# main_pcb_v2.net
KiCad netlist of a schematic drawn in EAGLE
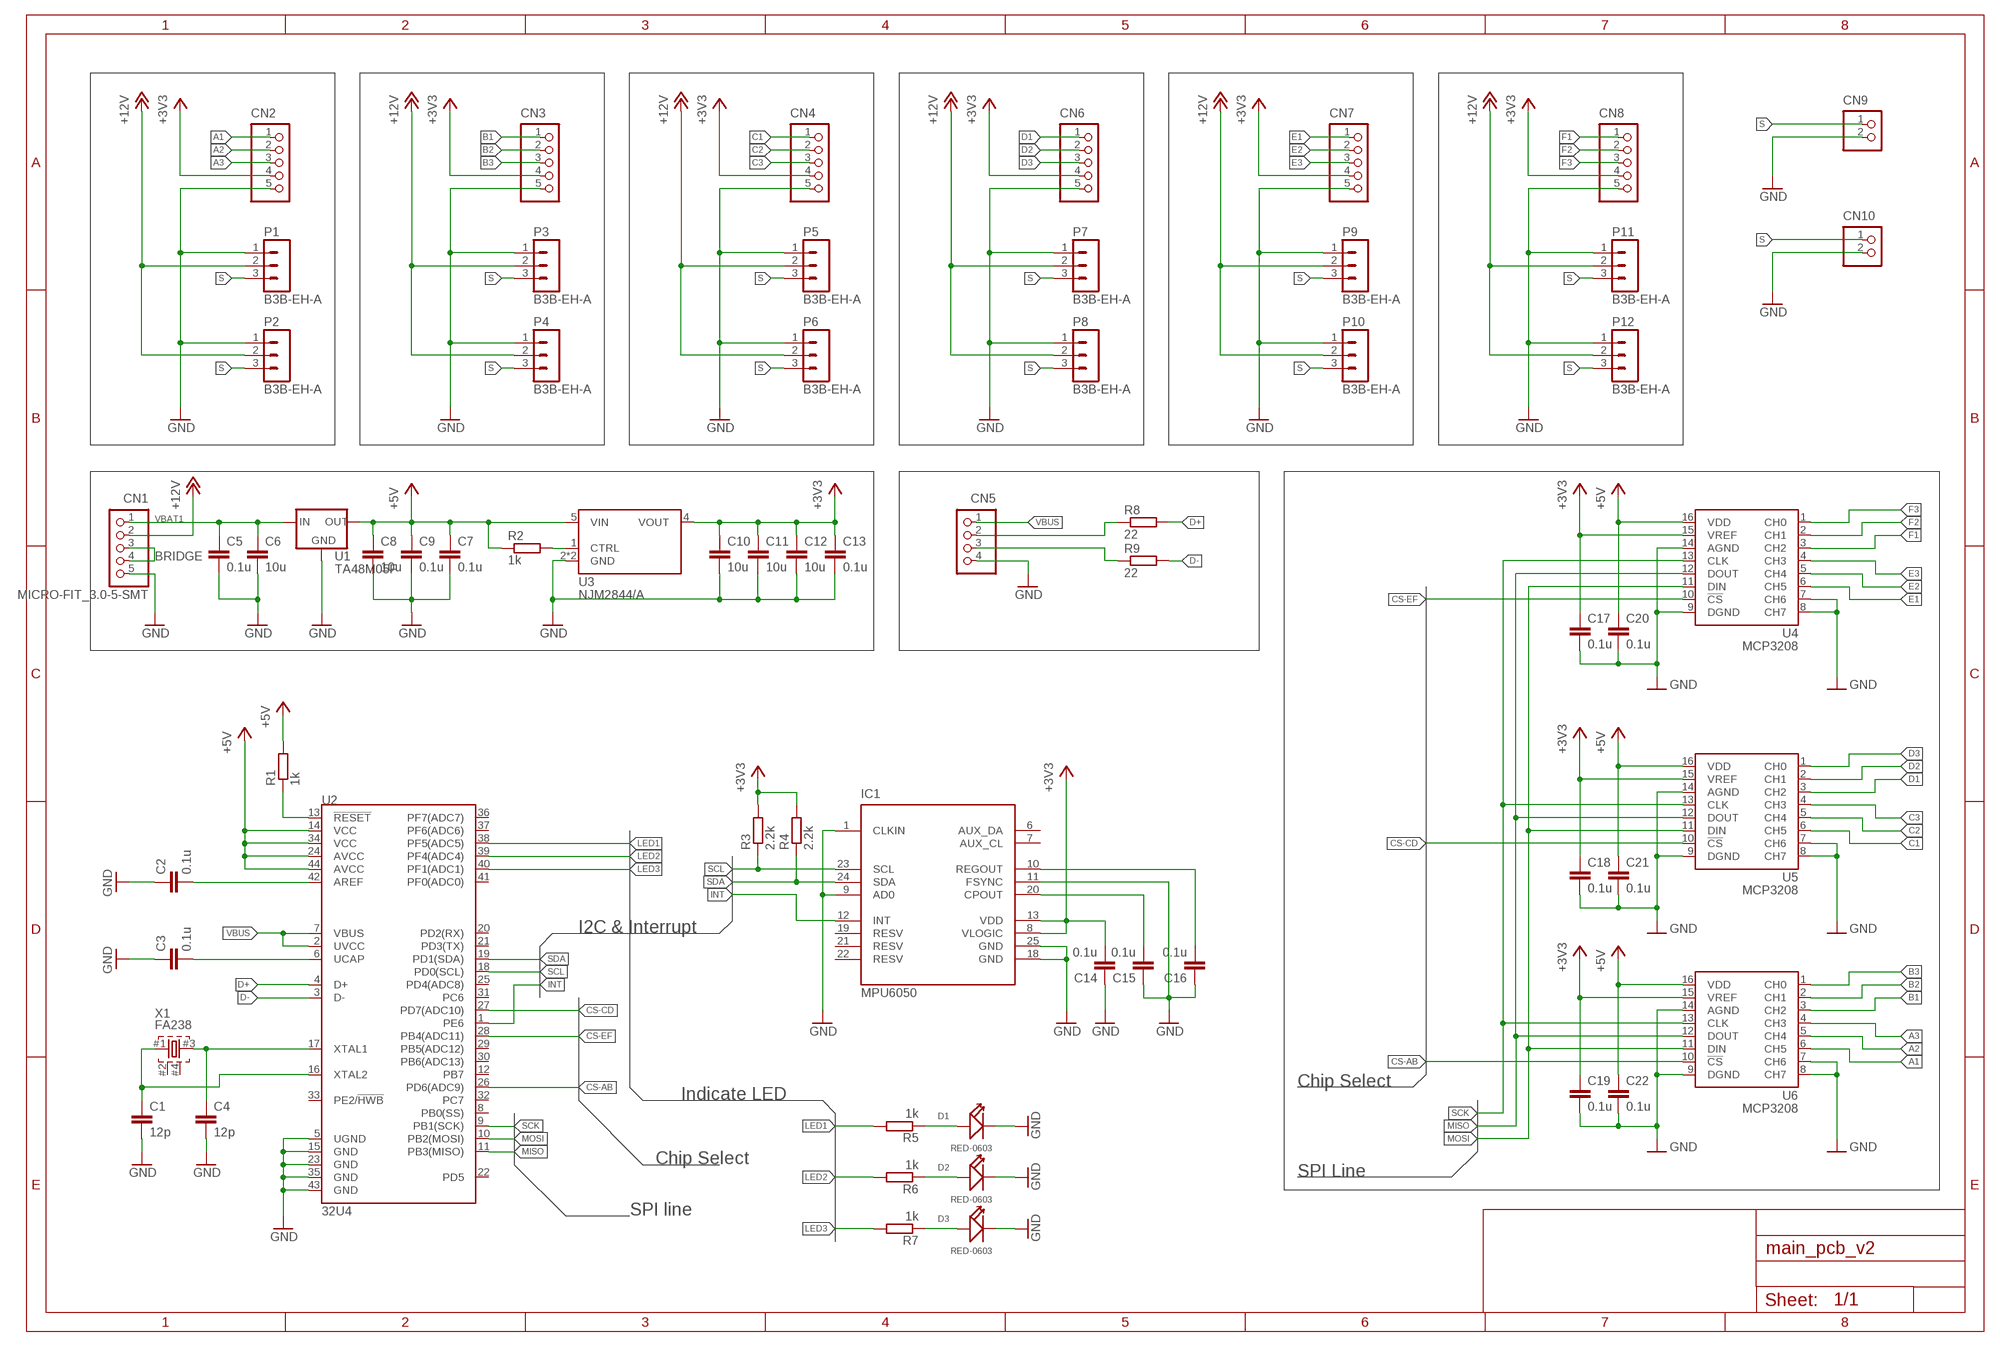
[diagram p0: schematic, sheet 1]

(export (version "E")
  (design (tool "Eeschema 10.0.6"))
  (components
    (comp (ref "C1")
      (value "12p")
      (footprint "eagle-import:C0603")
      (libsource (lib "eagle-import") (part "C-EUC0603"))
    )
    (comp (ref "C2")
      (value "0.1u")
      (footprint "eagle-import:C0603")
      (libsource (lib "eagle-import") (part "C-EUC0603"))
    )
    (comp (ref "C3")
      (value "0.1u")
      (footprint "eagle-import:C0603")
      (libsource (lib "eagle-import") (part "C-EUC0603"))
    )
    (comp (ref "C4")
      (value "12p")
      (footprint "eagle-import:C0603")
      (libsource (lib "eagle-import") (part "C-EUC0603"))
    )
    (comp (ref "C5")
      (value "0.1u")
      (footprint "eagle-import:C0603")
      (libsource (lib "eagle-import") (part "C-EUC0603"))
    )
    (comp (ref "C6")
      (value "10u")
      (footprint "eagle-import:C0805")
      (libsource (lib "eagle-import") (part "C-EUC0805"))
    )
    (comp (ref "C7")
      (value "0.1u")
      (footprint "eagle-import:C0603")
      (libsource (lib "eagle-import") (part "C-EUC0603"))
    )
    (comp (ref "C8")
      (value "10u")
      (footprint "eagle-import:C0805")
      (libsource (lib "eagle-import") (part "C-EUC0805"))
    )
    (comp (ref "C9")
      (value "0.1u")
      (footprint "eagle-import:C0603")
      (libsource (lib "eagle-import") (part "C-EUC0603"))
    )
    (comp (ref "C10")
      (value "10u")
      (footprint "eagle-import:C0805")
      (libsource (lib "eagle-import") (part "C-EUC0805"))
    )
    (comp (ref "C11")
      (value "10u")
      (footprint "eagle-import:C0805")
      (libsource (lib "eagle-import") (part "C-EUC0805"))
    )
    (comp (ref "C12")
      (value "10u")
      (footprint "eagle-import:C0805")
      (libsource (lib "eagle-import") (part "C-EUC0805"))
    )
    (comp (ref "C13")
      (value "0.1u")
      (footprint "eagle-import:C0603")
      (libsource (lib "eagle-import") (part "C-EUC0603"))
    )
    (comp (ref "C14")
      (value "0.1u")
      (footprint "eagle-import:C0603")
      (libsource (lib "eagle-import") (part "C-EUC0603"))
    )
    (comp (ref "C15")
      (value "0.1u")
      (footprint "eagle-import:C0603")
      (libsource (lib "eagle-import") (part "C-EUC0603"))
    )
    (comp (ref "C16")
      (value "0.1u")
      (footprint "eagle-import:C0603")
      (libsource (lib "eagle-import") (part "C-EUC0603"))
    )
    (comp (ref "C17")
      (value "0.1u")
      (footprint "eagle-import:C0603")
      (libsource (lib "eagle-import") (part "C-EUC0603"))
    )
    (comp (ref "C18")
      (value "0.1u")
      (footprint "eagle-import:C0603")
      (libsource (lib "eagle-import") (part "C-EUC0603"))
    )
    (comp (ref "C19")
      (value "0.1u")
      (footprint "eagle-import:C0603")
      (libsource (lib "eagle-import") (part "C-EUC0603"))
    )
    (comp (ref "C20")
      (value "0.1u")
      (footprint "eagle-import:C0603")
      (libsource (lib "eagle-import") (part "C-EUC0603"))
    )
    (comp (ref "C21")
      (value "0.1u")
      (footprint "eagle-import:C0603")
      (libsource (lib "eagle-import") (part "C-EUC0603"))
    )
    (comp (ref "C22")
      (value "0.1u")
      (footprint "eagle-import:C0603")
      (libsource (lib "eagle-import") (part "C-EUC0603"))
    )
    (comp (ref "CN1")
      (value "MICRO-FIT_3.0-5-SMT")
      (footprint "eagle-import:MICRO-FIT_3.0-5_SMT")
      (libsource (lib "eagle-import") (part "MICRO-FIT_3.0-5-SMT"))
    )
    (comp (ref "CN2")
      (value "B5B-PH-K-S")
      (footprint "eagle-import:B5B-PH-K-S")
      (libsource (lib "eagle-import") (part "B5B-PH-K-S"))
    )
    (comp (ref "CN3")
      (value "B5B-PH-K-S")
      (footprint "eagle-import:B5B-PH-K-S")
      (libsource (lib "eagle-import") (part "B5B-PH-K-S"))
    )
    (comp (ref "CN4")
      (value "B5B-PH-K-S")
      (footprint "eagle-import:B5B-PH-K-S")
      (libsource (lib "eagle-import") (part "B5B-PH-K-S"))
    )
    (comp (ref "CN5")
      (value "S4B-PH-K-S")
      (footprint "eagle-import:S4B-PH-K-S")
      (libsource (lib "eagle-import") (part "S4B-PH-K-S"))
    )
    (comp (ref "CN6")
      (value "B5B-PH-K-S")
      (footprint "eagle-import:B5B-PH-K-S")
      (libsource (lib "eagle-import") (part "B5B-PH-K-S"))
    )
    (comp (ref "CN7")
      (value "B5B-PH-K-S")
      (footprint "eagle-import:B5B-PH-K-S")
      (libsource (lib "eagle-import") (part "B5B-PH-K-S"))
    )
    (comp (ref "CN8")
      (value "B5B-PH-K-S")
      (footprint "eagle-import:B5B-PH-K-S")
      (libsource (lib "eagle-import") (part "B5B-PH-K-S"))
    )
    (comp (ref "CN9")
      (value "B2B-PH-K-S")
      (footprint "eagle-import:B2B-PH-K-S")
      (libsource (lib "eagle-import") (part "B2B-PH-K-S"))
    )
    (comp (ref "CN10")
      (value "B2B-PH-K-S")
      (footprint "eagle-import:B2B-PH-K-S")
      (libsource (lib "eagle-import") (part "B2B-PH-K-S"))
    )
    (comp (ref "D1")
      (value "RED-0603")
      (footprint "eagle-import:LED-0603")
      (fields (field (name "MPN") "19-217-R6C-AL1M2VY-3T"))
      (libsource (lib "eagle-import") (part "LED-SMD-RED-DIFFUSED(0603)"))
    )
    (comp (ref "D2")
      (value "RED-0603")
      (footprint "eagle-import:LED-0603")
      (fields (field (name "MPN") "19-217-R6C-AL1M2VY-3T"))
      (libsource (lib "eagle-import") (part "LED-SMD-RED-DIFFUSED(0603)"))
    )
    (comp (ref "D3")
      (value "RED-0603")
      (footprint "eagle-import:LED-0603")
      (fields (field (name "MPN") "19-217-R6C-AL1M2VY-3T"))
      (libsource (lib "eagle-import") (part "LED-SMD-RED-DIFFUSED(0603)"))
    )
    (comp (ref "IC1")
      (value "MPU6050")
      (footprint "eagle-import:QFN50P400X400X95-25T265X275N")
      (libsource (lib "eagle-import") (part "MPU6050"))
    )
    (comp (ref "P1")
      (value "B3B-EH-A")
      (footprint "eagle-import:B3B-EH-A")
      (libsource (lib "eagle-import") (part "B3B-EH-A"))
    )
    (comp (ref "P2")
      (value "B3B-EH-A")
      (footprint "eagle-import:B3B-EH-A")
      (libsource (lib "eagle-import") (part "B3B-EH-A"))
    )
    (comp (ref "P3")
      (value "B3B-EH-A")
      (footprint "eagle-import:B3B-EH-A")
      (libsource (lib "eagle-import") (part "B3B-EH-A"))
    )
    (comp (ref "P4")
      (value "B3B-EH-A")
      (footprint "eagle-import:B3B-EH-A")
      (libsource (lib "eagle-import") (part "B3B-EH-A"))
    )
    (comp (ref "P5")
      (value "B3B-EH-A")
      (footprint "eagle-import:B3B-EH-A")
      (libsource (lib "eagle-import") (part "B3B-EH-A"))
    )
    (comp (ref "P6")
      (value "B3B-EH-A")
      (footprint "eagle-import:B3B-EH-A")
      (libsource (lib "eagle-import") (part "B3B-EH-A"))
    )
    (comp (ref "P7")
      (value "B3B-EH-A")
      (footprint "eagle-import:B3B-EH-A")
      (libsource (lib "eagle-import") (part "B3B-EH-A"))
    )
    (comp (ref "P8")
      (value "B3B-EH-A")
      (footprint "eagle-import:B3B-EH-A")
      (libsource (lib "eagle-import") (part "B3B-EH-A"))
    )
    (comp (ref "P9")
      (value "B3B-EH-A")
      (footprint "eagle-import:B3B-EH-A")
      (libsource (lib "eagle-import") (part "B3B-EH-A"))
    )
    (comp (ref "P10")
      (value "B3B-EH-A")
      (footprint "eagle-import:B3B-EH-A")
      (libsource (lib "eagle-import") (part "B3B-EH-A"))
    )
    (comp (ref "P11")
      (value "B3B-EH-A")
      (footprint "eagle-import:B3B-EH-A")
      (libsource (lib "eagle-import") (part "B3B-EH-A"))
    )
    (comp (ref "P12")
      (value "B3B-EH-A")
      (footprint "eagle-import:B3B-EH-A")
      (libsource (lib "eagle-import") (part "B3B-EH-A"))
    )
    (comp (ref "R1")
      (value "1k")
      (footprint "eagle-import:R0603")
      (libsource (lib "eagle-import") (part "R-EU_R0603"))
    )
    (comp (ref "R2")
      (value "1k")
      (footprint "eagle-import:R0603")
      (libsource (lib "eagle-import") (part "R-EU_R0603"))
    )
    (comp (ref "R3")
      (value "2.2k")
      (footprint "eagle-import:R0603")
      (libsource (lib "eagle-import") (part "R-EU_R0603"))
    )
    (comp (ref "R4")
      (value "2.2k")
      (footprint "eagle-import:R0603")
      (libsource (lib "eagle-import") (part "R-EU_R0603"))
    )
    (comp (ref "R5")
      (value "1k")
      (footprint "eagle-import:R0603")
      (libsource (lib "eagle-import") (part "R-EU_R0603"))
    )
    (comp (ref "R6")
      (value "1k")
      (footprint "eagle-import:R0603")
      (libsource (lib "eagle-import") (part "R-EU_R0603"))
    )
    (comp (ref "R7")
      (value "1k")
      (footprint "eagle-import:R0603")
      (libsource (lib "eagle-import") (part "R-EU_R0603"))
    )
    (comp (ref "R8")
      (value "22")
      (footprint "eagle-import:R0603")
      (libsource (lib "eagle-import") (part "R-EU_R0603"))
    )
    (comp (ref "R9")
      (value "22")
      (footprint "eagle-import:R0603")
      (libsource (lib "eagle-import") (part "R-EU_R0603"))
    )
    (comp (ref "U1")
      (value "TA48M05F")
      (footprint "eagle-import:HSOP3-P-2.30A")
      (libsource (lib "eagle-import") (part "TA48M05F"))
    )
    (comp (ref "U2")
      (value "32U4")
      (footprint "eagle-import:TQFP44")
      (libsource (lib "eagle-import") (part "ATMEGA32U4_NOARDTQFP-44"))
    )
    (comp (ref "U3")
      (value "NJM2844/A")
      (footprint "eagle-import:SOT-89-5")
      (libsource (lib "eagle-import") (part "NJM2844/A"))
    )
    (comp (ref "U4")
      (value "MCP3208")
      (footprint "eagle-import:SO16")
      (libsource (lib "eagle-import") (part "MCP3208"))
    )
    (comp (ref "U5")
      (value "MCP3208")
      (footprint "eagle-import:SO16")
      (libsource (lib "eagle-import") (part "MCP3208"))
    )
    (comp (ref "U6")
      (value "MCP3208")
      (footprint "eagle-import:SO16")
      (libsource (lib "eagle-import") (part "MCP3208"))
    )
    (comp (ref "X1")
      (value "FA238")
      (footprint "eagle-import:OSC-FA238")
      (libsource (lib "eagle-import") (part "FA238"))
    )
  )
  (nets
    (net (code "1") (name "+3V3") (class "Default")
      (node (ref "C10") (pin "1") (pinfunction "1_1") (pintype "passive"))
      (node (ref "C11") (pin "1") (pinfunction "1_1") (pintype "passive"))
      (node (ref "C12") (pin "1") (pinfunction "1_1") (pintype "passive"))
      (node (ref "C13") (pin "1") (pinfunction "1_1") (pintype "passive"))
      (node (ref "C14") (pin "2") (pinfunction "2_2") (pintype "passive"))
      (node (ref "C17") (pin "1") (pinfunction "1_1") (pintype "passive"))
      (node (ref "C18") (pin "1") (pinfunction "1_1") (pintype "passive"))
      (node (ref "C19") (pin "1") (pinfunction "1_1") (pintype "passive"))
      (node (ref "CN2") (pin "4") (pinfunction "4_4") (pintype "passive"))
      (node (ref "CN3") (pin "4") (pinfunction "4_4") (pintype "passive"))
      (node (ref "CN4") (pin "4") (pinfunction "4_4") (pintype "passive"))
      (node (ref "CN6") (pin "4") (pinfunction "4_4") (pintype "passive"))
      (node (ref "CN7") (pin "4") (pinfunction "4_4") (pintype "passive"))
      (node (ref "CN8") (pin "4") (pinfunction "4_4") (pintype "passive"))
      (node (ref "IC1") (pin "13") (pinfunction "VDD_13") (pintype "power_in"))
      (node (ref "IC1") (pin "8") (pinfunction "VLOGIC_8") (pintype "power_in"))
      (node (ref "R3") (pin "2") (pinfunction "2_2") (pintype "passive"))
      (node (ref "R4") (pin "2") (pinfunction "2_2") (pintype "passive"))
      (node (ref "U3") (pin "4") (pinfunction "VOUT_4") (pintype "bidirectional"))
      (node (ref "U4") (pin "15") (pinfunction "VREF_15") (pintype "input"))
      (node (ref "U5") (pin "15") (pinfunction "VREF_15") (pintype "input"))
      (node (ref "U6") (pin "15") (pinfunction "VREF_15") (pintype "input"))
    )
    (net (code "2") (name "+5V") (class "Default")
      (node (ref "C20") (pin "1") (pinfunction "1_1") (pintype "passive"))
      (node (ref "C21") (pin "1") (pinfunction "1_1") (pintype "passive"))
      (node (ref "C22") (pin "1") (pinfunction "1_1") (pintype "passive"))
      (node (ref "C7") (pin "1") (pinfunction "1_1") (pintype "passive"))
      (node (ref "C8") (pin "1") (pinfunction "1_1") (pintype "passive"))
      (node (ref "C9") (pin "1") (pinfunction "1_1") (pintype "passive"))
      (node (ref "R1") (pin "2") (pinfunction "2_2") (pintype "passive"))
      (node (ref "R2") (pin "1") (pinfunction "1_1") (pintype "passive"))
      (node (ref "U1") (pin "2") (pinfunction "OUT_2") (pintype "passive"))
      (node (ref "U2") (pin "14") (pinfunction "VCC_14") (pintype "bidirectional"))
      (node (ref "U2") (pin "24") (pinfunction "AVCC_24") (pintype "bidirectional"))
      (node (ref "U2") (pin "34") (pinfunction "VCC_34") (pintype "bidirectional"))
      (node (ref "U2") (pin "44") (pinfunction "AVCC_44") (pintype "bidirectional"))
      (node (ref "U3") (pin "5") (pinfunction "VIN_5") (pintype "bidirectional"))
      (node (ref "U4") (pin "16") (pinfunction "VDD_16") (pintype "power_in"))
      (node (ref "U5") (pin "16") (pinfunction "VDD_16") (pintype "power_in"))
      (node (ref "U6") (pin "16") (pinfunction "VDD_16") (pintype "power_in"))
    )
    (net (code "3") (name "+12V") (class "Default")
      (node (ref "CN1") (pin "2") (pinfunction "2_2") (pintype "passive"))
      (node (ref "P1") (pin "2") (pinfunction "2_2") (pintype "passive"))
      (node (ref "P10") (pin "2") (pinfunction "2_2") (pintype "passive"))
      (node (ref "P11") (pin "2") (pinfunction "2_2") (pintype "passive"))
      (node (ref "P12") (pin "2") (pinfunction "2_2") (pintype "passive"))
      (node (ref "P2") (pin "2") (pinfunction "2_2") (pintype "passive"))
      (node (ref "P3") (pin "2") (pinfunction "2_2") (pintype "passive"))
      (node (ref "P4") (pin "2") (pinfunction "2_2") (pintype "passive"))
      (node (ref "P5") (pin "2") (pinfunction "2_2") (pintype "passive"))
      (node (ref "P6") (pin "2") (pinfunction "2_2") (pintype "passive"))
      (node (ref "P7") (pin "2") (pinfunction "2_2") (pintype "passive"))
      (node (ref "P8") (pin "2") (pinfunction "2_2") (pintype "passive"))
      (node (ref "P9") (pin "2") (pinfunction "2_2") (pintype "passive"))
    )
    (net (code "4") (name "/BRIDGE") (class "Default")
      (node (ref "CN1") (pin "3") (pinfunction "3_3") (pintype "passive"))
      (node (ref "CN1") (pin "4") (pinfunction "4_4") (pintype "passive"))
    )
    (net (code "5") (name "/VBAT1") (class "Default")
      (node (ref "C5") (pin "1") (pinfunction "1_1") (pintype "passive"))
      (node (ref "C6") (pin "1") (pinfunction "1_1") (pintype "passive"))
      (node (ref "CN1") (pin "1") (pinfunction "1_1") (pintype "passive"))
      (node (ref "U1") (pin "1") (pinfunction "IN_1") (pintype "input"))
    )
    (net (code "6") (name "A1") (class "Default")
      (node (ref "CN2") (pin "1") (pinfunction "1_1") (pintype "passive"))
      (node (ref "U6") (pin "6") (pinfunction "CH5_6") (pintype "input"))
    )
    (net (code "7") (name "A2") (class "Default")
      (node (ref "CN2") (pin "2") (pinfunction "2_2") (pintype "passive"))
      (node (ref "U6") (pin "5") (pinfunction "CH4_5") (pintype "input"))
    )
    (net (code "8") (name "A3") (class "Default")
      (node (ref "CN2") (pin "3") (pinfunction "3_3") (pintype "passive"))
      (node (ref "U6") (pin "4") (pinfunction "CH3_4") (pintype "input"))
    )
    (net (code "9") (name "B1") (class "Default")
      (node (ref "CN3") (pin "1") (pinfunction "1_1") (pintype "passive"))
      (node (ref "U6") (pin "3") (pinfunction "CH2_3") (pintype "input"))
    )
    (net (code "10") (name "B2") (class "Default")
      (node (ref "CN3") (pin "2") (pinfunction "2_2") (pintype "passive"))
      (node (ref "U6") (pin "2") (pinfunction "CH1_2") (pintype "input"))
    )
    (net (code "11") (name "B3") (class "Default")
      (node (ref "CN3") (pin "3") (pinfunction "3_3") (pintype "passive"))
      (node (ref "U6") (pin "1") (pinfunction "CH0_1") (pintype "input"))
    )
    (net (code "12") (name "C1") (class "Default")
      (node (ref "CN4") (pin "1") (pinfunction "1_1") (pintype "passive"))
      (node (ref "U5") (pin "6") (pinfunction "CH5_6") (pintype "input"))
    )
    (net (code "13") (name "C2") (class "Default")
      (node (ref "CN4") (pin "2") (pinfunction "2_2") (pintype "passive"))
      (node (ref "U5") (pin "5") (pinfunction "CH4_5") (pintype "input"))
    )
    (net (code "14") (name "C3") (class "Default")
      (node (ref "CN4") (pin "3") (pinfunction "3_3") (pintype "passive"))
      (node (ref "U5") (pin "4") (pinfunction "CH3_4") (pintype "input"))
    )
    (net (code "15") (name "CS-AB") (class "Default")
      (node (ref "U2") (pin "26") (pinfunction "PD6(ADC9)_26") (pintype "bidirectional"))
      (node (ref "U6") (pin "10") (pinfunction "~{CS}_10") (pintype "input"))
    )
    (net (code "16") (name "CS-CD") (class "Default")
      (node (ref "U2") (pin "27") (pinfunction "PD7(ADC10)_27") (pintype "bidirectional"))
      (node (ref "U5") (pin "10") (pinfunction "~{CS}_10") (pintype "input"))
    )
    (net (code "17") (name "CS-EF") (class "Default")
      (node (ref "U2") (pin "28") (pinfunction "PB4(ADC11)_28") (pintype "bidirectional"))
      (node (ref "U4") (pin "10") (pinfunction "~{CS}_10") (pintype "input"))
    )
    (net (code "18") (name "D+") (class "Default")
      (node (ref "R8") (pin "2") (pinfunction "2_2") (pintype "passive"))
      (node (ref "U2") (pin "4") (pinfunction "D+_4") (pintype "bidirectional"))
    )
    (net (code "19") (name "D-") (class "Default")
      (node (ref "R9") (pin "2") (pinfunction "2_2") (pintype "passive"))
      (node (ref "U2") (pin "3") (pinfunction "D-_3") (pintype "bidirectional"))
    )
    (net (code "20") (name "D1") (class "Default")
      (node (ref "CN6") (pin "1") (pinfunction "1_1") (pintype "passive"))
      (node (ref "U5") (pin "3") (pinfunction "CH2_3") (pintype "input"))
    )
    (net (code "21") (name "D2") (class "Default")
      (node (ref "CN6") (pin "2") (pinfunction "2_2") (pintype "passive"))
      (node (ref "U5") (pin "2") (pinfunction "CH1_2") (pintype "input"))
    )
    (net (code "22") (name "D3") (class "Default")
      (node (ref "CN6") (pin "3") (pinfunction "3_3") (pintype "passive"))
      (node (ref "U5") (pin "1") (pinfunction "CH0_1") (pintype "input"))
    )
    (net (code "23") (name "E1") (class "Default")
      (node (ref "CN7") (pin "1") (pinfunction "1_1") (pintype "passive"))
      (node (ref "U4") (pin "6") (pinfunction "CH5_6") (pintype "input"))
    )
    (net (code "24") (name "E2") (class "Default")
      (node (ref "CN7") (pin "2") (pinfunction "2_2") (pintype "passive"))
      (node (ref "U4") (pin "5") (pinfunction "CH4_5") (pintype "input"))
    )
    (net (code "25") (name "E3") (class "Default")
      (node (ref "CN7") (pin "3") (pinfunction "3_3") (pintype "passive"))
      (node (ref "U4") (pin "4") (pinfunction "CH3_4") (pintype "input"))
    )
    (net (code "26") (name "F1") (class "Default")
      (node (ref "CN8") (pin "1") (pinfunction "1_1") (pintype "passive"))
      (node (ref "U4") (pin "3") (pinfunction "CH2_3") (pintype "input"))
    )
    (net (code "27") (name "F2") (class "Default")
      (node (ref "CN8") (pin "2") (pinfunction "2_2") (pintype "passive"))
      (node (ref "U4") (pin "2") (pinfunction "CH1_2") (pintype "input"))
    )
    (net (code "28") (name "F3") (class "Default")
      (node (ref "CN8") (pin "3") (pinfunction "3_3") (pintype "passive"))
      (node (ref "U4") (pin "1") (pinfunction "CH0_1") (pintype "input"))
    )
    (net (code "29") (name "GND") (class "Default")
      (node (ref "C1") (pin "2") (pinfunction "2_2") (pintype "passive"))
      (node (ref "C10") (pin "2") (pinfunction "2_2") (pintype "passive"))
      (node (ref "C11") (pin "2") (pinfunction "2_2") (pintype "passive"))
      (node (ref "C12") (pin "2") (pinfunction "2_2") (pintype "passive"))
      (node (ref "C13") (pin "2") (pinfunction "2_2") (pintype "passive"))
      (node (ref "C14") (pin "1") (pinfunction "1_1") (pintype "passive"))
      (node (ref "C15") (pin "1") (pinfunction "1_1") (pintype "passive"))
      (node (ref "C16") (pin "1") (pinfunction "1_1") (pintype "passive"))
      (node (ref "C17") (pin "2") (pinfunction "2_2") (pintype "passive"))
      (node (ref "C18") (pin "2") (pinfunction "2_2") (pintype "passive"))
      (node (ref "C19") (pin "2") (pinfunction "2_2") (pintype "passive"))
      (node (ref "C2") (pin "1") (pinfunction "1_1") (pintype "passive"))
      (node (ref "C20") (pin "2") (pinfunction "2_2") (pintype "passive"))
      (node (ref "C21") (pin "2") (pinfunction "2_2") (pintype "passive"))
      (node (ref "C22") (pin "2") (pinfunction "2_2") (pintype "passive"))
      (node (ref "C3") (pin "1") (pinfunction "1_1") (pintype "passive"))
      (node (ref "C4") (pin "2") (pinfunction "2_2") (pintype "passive"))
      (node (ref "C5") (pin "2") (pinfunction "2_2") (pintype "passive"))
      (node (ref "C6") (pin "2") (pinfunction "2_2") (pintype "passive"))
      (node (ref "C7") (pin "2") (pinfunction "2_2") (pintype "passive"))
      (node (ref "C8") (pin "2") (pinfunction "2_2") (pintype "passive"))
      (node (ref "C9") (pin "2") (pinfunction "2_2") (pintype "passive"))
      (node (ref "CN1") (pin "5") (pinfunction "5_5") (pintype "passive"))
      (node (ref "CN10") (pin "2") (pinfunction "2_2") (pintype "passive"))
      (node (ref "CN2") (pin "5") (pinfunction "5_5") (pintype "passive"))
      (node (ref "CN3") (pin "5") (pinfunction "5_5") (pintype "passive"))
      (node (ref "CN4") (pin "5") (pinfunction "5_5") (pintype "passive"))
      (node (ref "CN5") (pin "4") (pinfunction "4_4") (pintype "passive"))
      (node (ref "CN6") (pin "5") (pinfunction "5_5") (pintype "passive"))
      (node (ref "CN7") (pin "5") (pinfunction "5_5") (pintype "passive"))
      (node (ref "CN8") (pin "5") (pinfunction "5_5") (pintype "passive"))
      (node (ref "CN9") (pin "2") (pinfunction "2_2") (pintype "passive"))
      (node (ref "D1") (pin "-") (pinfunction "-_-") (pintype "passive"))
      (node (ref "D2") (pin "-") (pinfunction "-_-") (pintype "passive"))
      (node (ref "D3") (pin "-") (pinfunction "-_-") (pintype "passive"))
      (node (ref "IC1") (pin "1") (pinfunction "CLKIN_1") (pintype "input"))
      (node (ref "IC1") (pin "11") (pinfunction "FSYNC_11") (pintype "input"))
      (node (ref "IC1") (pin "18") (pinfunction "GND_18") (pintype "power_in"))
      (node (ref "IC1") (pin "25") (pinfunction "GND_25") (pintype "power_in"))
      (node (ref "IC1") (pin "9") (pinfunction "AD0_9") (pintype "input"))
      (node (ref "P1") (pin "1") (pinfunction "1_1") (pintype "passive"))
      (node (ref "P10") (pin "1") (pinfunction "1_1") (pintype "passive"))
      (node (ref "P11") (pin "1") (pinfunction "1_1") (pintype "passive"))
      (node (ref "P12") (pin "1") (pinfunction "1_1") (pintype "passive"))
      (node (ref "P2") (pin "1") (pinfunction "1_1") (pintype "passive"))
      (node (ref "P3") (pin "1") (pinfunction "1_1") (pintype "passive"))
      (node (ref "P4") (pin "1") (pinfunction "1_1") (pintype "passive"))
      (node (ref "P5") (pin "1") (pinfunction "1_1") (pintype "passive"))
      (node (ref "P6") (pin "1") (pinfunction "1_1") (pintype "passive"))
      (node (ref "P7") (pin "1") (pinfunction "1_1") (pintype "passive"))
      (node (ref "P8") (pin "1") (pinfunction "1_1") (pintype "passive"))
      (node (ref "P9") (pin "1") (pinfunction "1_1") (pintype "passive"))
      (node (ref "U1") (pin "3") (pinfunction "GND_3") (pintype "input"))
      (node (ref "U2") (pin "15") (pinfunction "GND_15") (pintype "bidirectional"))
      (node (ref "U2") (pin "23") (pinfunction "GND_23") (pintype "bidirectional"))
      (node (ref "U2") (pin "35") (pinfunction "GND_35") (pintype "bidirectional"))
      (node (ref "U2") (pin "43") (pinfunction "GND_43") (pintype "bidirectional"))
      (node (ref "U2") (pin "5") (pinfunction "UGND_5") (pintype "bidirectional"))
      (node (ref "U3") (pin "2") (pinfunction "GND_2") (pintype "bidirectional"))
      (node (ref "U3") (pin "2'") (pinfunction "GND_2'") (pintype "bidirectional"))
      (node (ref "U4") (pin "14") (pinfunction "AGND_14") (pintype "power_in"))
      (node (ref "U4") (pin "7") (pinfunction "CH6_7") (pintype "input"))
      (node (ref "U4") (pin "8") (pinfunction "CH7_8") (pintype "input"))
      (node (ref "U4") (pin "9") (pinfunction "DGND_9") (pintype "power_in"))
      (node (ref "U5") (pin "14") (pinfunction "AGND_14") (pintype "power_in"))
      (node (ref "U5") (pin "7") (pinfunction "CH6_7") (pintype "input"))
      (node (ref "U5") (pin "8") (pinfunction "CH7_8") (pintype "input"))
      (node (ref "U5") (pin "9") (pinfunction "DGND_9") (pintype "power_in"))
      (node (ref "U6") (pin "14") (pinfunction "AGND_14") (pintype "power_in"))
      (node (ref "U6") (pin "7") (pinfunction "CH6_7") (pintype "input"))
      (node (ref "U6") (pin "8") (pinfunction "CH7_8") (pintype "input"))
      (node (ref "U6") (pin "9") (pinfunction "DGND_9") (pintype "power_in"))
    )
    (net (code "30") (name "INT") (class "Default")
      (node (ref "IC1") (pin "12") (pinfunction "INT_12") (pintype "open_collector"))
      (node (ref "U2") (pin "1") (pinfunction "PE6_1") (pintype "bidirectional"))
    )
    (net (code "31") (name "LED1") (class "Default")
      (node (ref "R5") (pin "2") (pinfunction "2_2") (pintype "passive"))
      (node (ref "U2") (pin "38") (pinfunction "PF5(ADC5)_38") (pintype "bidirectional"))
    )
    (net (code "32") (name "LED2") (class "Default")
      (node (ref "R6") (pin "2") (pinfunction "2_2") (pintype "passive"))
      (node (ref "U2") (pin "39") (pinfunction "PF4(ADC4)_39") (pintype "bidirectional"))
    )
    (net (code "33") (name "LED3") (class "Default")
      (node (ref "R7") (pin "2") (pinfunction "2_2") (pintype "passive"))
      (node (ref "U2") (pin "40") (pinfunction "PF1(ADC1)_40") (pintype "bidirectional"))
    )
    (net (code "34") (name "MISO") (class "Default")
      (node (ref "U2") (pin "11") (pinfunction "PB3(MISO)_11") (pintype "bidirectional"))
      (node (ref "U4") (pin "12") (pinfunction "DOUT_12") (pintype "output"))
      (node (ref "U5") (pin "12") (pinfunction "DOUT_12") (pintype "output"))
      (node (ref "U6") (pin "12") (pinfunction "DOUT_12") (pintype "output"))
    )
    (net (code "35") (name "MOSI") (class "Default")
      (node (ref "U2") (pin "10") (pinfunction "PB2(MOSI)_10") (pintype "bidirectional"))
      (node (ref "U4") (pin "11") (pinfunction "DIN_11") (pintype "input"))
      (node (ref "U5") (pin "11") (pinfunction "DIN_11") (pintype "input"))
      (node (ref "U6") (pin "11") (pinfunction "DIN_11") (pintype "input"))
    )
    (net (code "36") (name "Net-(CN5-Pad2)") (class "Default")
      (node (ref "CN5") (pin "2") (pinfunction "2_2") (pintype "passive"))
      (node (ref "R8") (pin "1") (pinfunction "1_1") (pintype "passive"))
    )
    (net (code "37") (name "Net-(CN5-Pad3)") (class "Default")
      (node (ref "CN5") (pin "3") (pinfunction "3_3") (pintype "passive"))
      (node (ref "R9") (pin "1") (pinfunction "1_1") (pintype "passive"))
    )
    (net (code "38") (name "Net-(D1-Pad+)") (class "Default")
      (node (ref "D1") (pin "+") (pinfunction "+_+") (pintype "passive"))
      (node (ref "R5") (pin "1") (pinfunction "1_1") (pintype "passive"))
    )
    (net (code "39") (name "Net-(D2-Pad+)") (class "Default")
      (node (ref "D2") (pin "+") (pinfunction "+_+") (pintype "passive"))
      (node (ref "R6") (pin "1") (pinfunction "1_1") (pintype "passive"))
    )
    (net (code "40") (name "Net-(D3-Pad+)") (class "Default")
      (node (ref "D3") (pin "+") (pinfunction "+_+") (pintype "passive"))
      (node (ref "R7") (pin "1") (pinfunction "1_1") (pintype "passive"))
    )
    (net (code "41") (name "Net-(IC1A-CPOUT)") (class "Default")
      (node (ref "C15") (pin "2") (pinfunction "2_2") (pintype "passive"))
      (node (ref "IC1") (pin "20") (pinfunction "CPOUT_20") (pintype "output"))
    )
    (net (code "42") (name "Net-(IC1A-REGOUT)") (class "Default")
      (node (ref "C16") (pin "2") (pinfunction "2_2") (pintype "passive"))
      (node (ref "IC1") (pin "10") (pinfunction "REGOUT_10") (pintype "output"))
    )
    (net (code "43") (name "Net-(U2-AREF)") (class "Default")
      (node (ref "C2") (pin "2") (pinfunction "2_2") (pintype "passive"))
      (node (ref "U2") (pin "42") (pinfunction "AREF_42") (pintype "bidirectional"))
    )
    (net (code "44") (name "Net-(U2-UCAP)") (class "Default")
      (node (ref "C3") (pin "2") (pinfunction "2_2") (pintype "passive"))
      (node (ref "U2") (pin "6") (pinfunction "UCAP_6") (pintype "bidirectional"))
    )
    (net (code "45") (name "Net-(U2-XTAL1)") (class "Default")
      (node (ref "C4") (pin "1") (pinfunction "1_1") (pintype "passive"))
      (node (ref "U2") (pin "17") (pinfunction "XTAL1_17") (pintype "bidirectional"))
      (node (ref "X1") (pin "#3") (pinfunction "3_#3") (pintype "passive"))
    )
    (net (code "46") (name "Net-(U2-XTAL2)") (class "Default")
      (node (ref "C1") (pin "1") (pinfunction "1_1") (pintype "passive"))
      (node (ref "U2") (pin "16") (pinfunction "XTAL2_16") (pintype "bidirectional"))
      (node (ref "X1") (pin "#1") (pinfunction "1_#1") (pintype "passive"))
    )
    (net (code "47") (name "Net-(U2-~{RESET})") (class "Default")
      (node (ref "R1") (pin "1") (pinfunction "1_1") (pintype "passive"))
      (node (ref "U2") (pin "13") (pinfunction "~{RESET}_13") (pintype "bidirectional"))
    )
    (net (code "48") (name "Net-(U3-CTRL)") (class "Default")
      (node (ref "R2") (pin "2") (pinfunction "2_2") (pintype "passive"))
      (node (ref "U3") (pin "1") (pinfunction "CTRL_1") (pintype "bidirectional"))
    )
    (net (code "49") (name "S") (class "Default")
      (node (ref "CN10") (pin "1") (pinfunction "1_1") (pintype "passive"))
      (node (ref "CN9") (pin "1") (pinfunction "1_1") (pintype "passive"))
      (node (ref "P1") (pin "3") (pinfunction "3_3") (pintype "passive"))
      (node (ref "P10") (pin "3") (pinfunction "3_3") (pintype "passive"))
      (node (ref "P11") (pin "3") (pinfunction "3_3") (pintype "passive"))
      (node (ref "P12") (pin "3") (pinfunction "3_3") (pintype "passive"))
      (node (ref "P2") (pin "3") (pinfunction "3_3") (pintype "passive"))
      (node (ref "P3") (pin "3") (pinfunction "3_3") (pintype "passive"))
      (node (ref "P4") (pin "3") (pinfunction "3_3") (pintype "passive"))
      (node (ref "P5") (pin "3") (pinfunction "3_3") (pintype "passive"))
      (node (ref "P6") (pin "3") (pinfunction "3_3") (pintype "passive"))
      (node (ref "P7") (pin "3") (pinfunction "3_3") (pintype "passive"))
      (node (ref "P8") (pin "3") (pinfunction "3_3") (pintype "passive"))
      (node (ref "P9") (pin "3") (pinfunction "3_3") (pintype "passive"))
    )
    (net (code "50") (name "SCK") (class "Default")
      (node (ref "U2") (pin "9") (pinfunction "PB1(SCK)_9") (pintype "bidirectional"))
      (node (ref "U4") (pin "13") (pinfunction "CLK_13") (pintype "input"))
      (node (ref "U5") (pin "13") (pinfunction "CLK_13") (pintype "input"))
      (node (ref "U6") (pin "13") (pinfunction "CLK_13") (pintype "input"))
    )
    (net (code "51") (name "SCL") (class "Default")
      (node (ref "IC1") (pin "23") (pinfunction "SCL_23") (pintype "input"))
      (node (ref "R3") (pin "1") (pinfunction "1_1") (pintype "passive"))
      (node (ref "U2") (pin "18") (pinfunction "PD0(SCL)_18") (pintype "bidirectional"))
    )
    (net (code "52") (name "SDA") (class "Default")
      (node (ref "IC1") (pin "24") (pinfunction "SDA_24") (pintype "bidirectional"))
      (node (ref "R4") (pin "1") (pinfunction "1_1") (pintype "passive"))
      (node (ref "U2") (pin "19") (pinfunction "PD1(SDA)_19") (pintype "bidirectional"))
    )
    (net (code "53") (name "VBUS") (class "Default")
      (node (ref "CN5") (pin "1") (pinfunction "1_1") (pintype "passive"))
      (node (ref "U2") (pin "2") (pinfunction "UVCC_2") (pintype "bidirectional"))
      (node (ref "U2") (pin "7") (pinfunction "VBUS_7") (pintype "bidirectional"))
    )
    (net (code "54") (name "unconnected-(IC1A-AUX_CL-Pad7)") (class "Default")
      (node (ref "IC1") (pin "7") (pinfunction "AUX_CL_7") (pintype "bidirectional"))
    )
    (net (code "55") (name "unconnected-(IC1A-AUX_DA-Pad6)") (class "Default")
      (node (ref "IC1") (pin "6") (pinfunction "AUX_DA_6") (pintype "bidirectional"))
    )
    (net (code "56") (name "unconnected-(IC1A-RESV-Pad19)") (class "Default")
      (node (ref "IC1") (pin "19") (pinfunction "RESV_19") (pintype "passive"))
    )
    (net (code "57") (name "unconnected-(IC1A-RESV-Pad21)") (class "Default")
      (node (ref "IC1") (pin "21") (pinfunction "RESV_21") (pintype "passive"))
    )
    (net (code "58") (name "unconnected-(IC1A-RESV-Pad22)") (class "Default")
      (node (ref "IC1") (pin "22") (pinfunction "RESV_22") (pintype "passive"))
    )
    (net (code "59") (name "unconnected-(U2-PB0(SS)-Pad8)") (class "Default")
      (node (ref "U2") (pin "8") (pinfunction "PB0(SS)_8") (pintype "bidirectional"))
    )
    (net (code "60") (name "unconnected-(U2-PB5(ADC12)-Pad29)") (class "Default")
      (node (ref "U2") (pin "29") (pinfunction "PB5(ADC12)_29") (pintype "bidirectional"))
    )
    (net (code "61") (name "unconnected-(U2-PB6(ADC13)-Pad30)") (class "Default")
      (node (ref "U2") (pin "30") (pinfunction "PB6(ADC13)_30") (pintype "bidirectional"))
    )
    (net (code "62") (name "unconnected-(U2-PB7-Pad12)") (class "Default")
      (node (ref "U2") (pin "12") (pinfunction "PB7_12") (pintype "bidirectional"))
    )
    (net (code "63") (name "unconnected-(U2-PC6-Pad31)") (class "Default")
      (node (ref "U2") (pin "31") (pinfunction "PC6_31") (pintype "bidirectional"))
    )
    (net (code "64") (name "unconnected-(U2-PC7-Pad32)") (class "Default")
      (node (ref "U2") (pin "32") (pinfunction "PC7_32") (pintype "bidirectional"))
    )
    (net (code "65") (name "unconnected-(U2-PD2(RX)-Pad20)") (class "Default")
      (node (ref "U2") (pin "20") (pinfunction "PD2(RX)_20") (pintype "bidirectional"))
    )
    (net (code "66") (name "unconnected-(U2-PD3(TX)-Pad21)") (class "Default")
      (node (ref "U2") (pin "21") (pinfunction "PD3(TX)_21") (pintype "bidirectional"))
    )
    (net (code "67") (name "unconnected-(U2-PD4(ADC8)-Pad25)") (class "Default")
      (node (ref "U2") (pin "25") (pinfunction "PD4(ADC8)_25") (pintype "bidirectional"))
    )
    (net (code "68") (name "unconnected-(U2-PD5-Pad22)") (class "Default")
      (node (ref "U2") (pin "22") (pinfunction "PD5_22") (pintype "bidirectional"))
    )
    (net (code "69") (name "unconnected-(U2-PE2{slash}~{HWB}-Pad33)") (class "Default")
      (node (ref "U2") (pin "33") (pinfunction "PE2/~{HWB}_33") (pintype "bidirectional"))
    )
    (net (code "70") (name "unconnected-(U2-PF0(ADC0)-Pad41)") (class "Default")
      (node (ref "U2") (pin "41") (pinfunction "PF0(ADC0)_41") (pintype "bidirectional"))
    )
    (net (code "71") (name "unconnected-(U2-PF6(ADC6)-Pad37)") (class "Default")
      (node (ref "U2") (pin "37") (pinfunction "PF6(ADC6)_37") (pintype "bidirectional"))
    )
    (net (code "72") (name "unconnected-(U2-PF7(ADC7)-Pad36)") (class "Default")
      (node (ref "U2") (pin "36") (pinfunction "PF7(ADC7)_36") (pintype "bidirectional"))
    )
    (net (code "73") (name "unconnected-(X1-2-Pad#2)") (class "Default")
      (node (ref "X1") (pin "#2") (pinfunction "2_#2") (pintype "passive"))
    )
    (net (code "74") (name "unconnected-(X1-4-Pad#4)") (class "Default")
      (node (ref "X1") (pin "#4") (pinfunction "4_#4") (pintype "passive"))
    )
  )
)
